# MotorCtrl2.net
KiCad netlist of a schematic drawn in Altium Designer
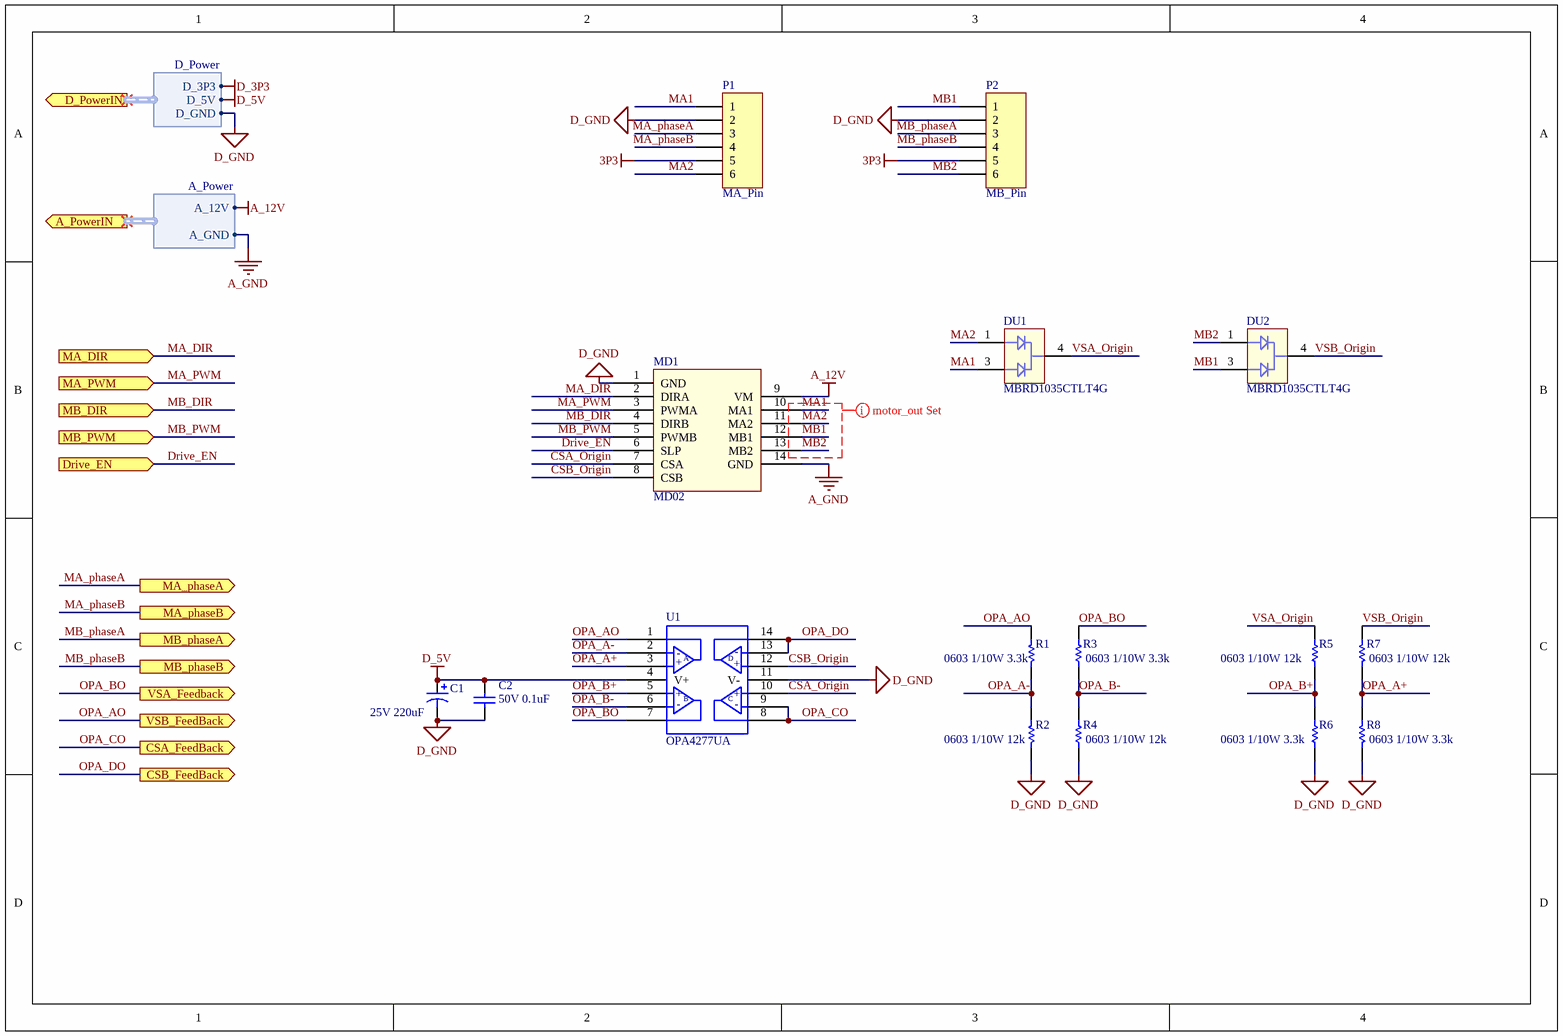
[diagram p0: MotorCtrl2.SchDoc]

(export (version "E")
  (design (tool "Eeschema 10.0.6"))
  (components
    (comp (ref "C1")
      (value "25V 220uF")
      (footprint "OWMR:VZT221M1ETR-0607")
      (fields (field (name "PUBLISHER") "Altium Limited"))
      (libsource (lib "Miscellaneous Devices") (part "Cap Pol1"))
    )
    (comp (ref "C2")
      (value "50V 0.1uF")
      (footprint "OWMR:0603F104M500NT")
      (description "50V 100nF Y5V ±20% 0603 Multilayer Ceramic Capacitors MLCC - SMD/SMT ROHS")
      (fields (field (name "PUBLISHER") "Altium Limited"))
      (libsource (lib "Miscellaneous Devices") (part "Cap Semi"))
    )
    (comp (ref "DU1")
      (value "MBRD1035CTLT4G")
      (footprint "OWMR:MBRD1035CTLT4G")
      (description "35V 470mV@5A 5A TO-252-2(DPAK) Schottky Barrier Diodes (SBD) ROHS")
      (libsource (lib "OWMR") (part "MBRD1035CTLT4G"))
    )
    (comp (ref "DU2")
      (value "MBRD1035CTLT4G")
      (footprint "OWMR:MBRD1035CTLT4G")
      (description "35V 470mV@5A 5A TO-252-2(DPAK) Schottky Barrier Diodes (SBD) ROHS")
      (libsource (lib "OWMR") (part "MBRD1035CTLT4G"))
    )
    (comp (ref "MD1")
      (value "MD02")
      (footprint "OWMR:MOTOR_DRIVER")
      (description "17A 2 Cheel Motor Driver")
      (libsource (lib "OWMR") (part "Motor Driver"))
    )
    (comp (ref "P1")
      (value "MA_Pin")
      (footprint "OWMR:S6B-XH-A")
      (description "S6B-XH-A")
      (fields (field (name "PUBLISHER") "Altium Limited"))
      (libsource (lib "Miscellaneous Connectors") (part "Header 6"))
    )
    (comp (ref "P2")
      (value "MB_Pin")
      (footprint "OWMR:S6B-XH-A")
      (description "S6B-XH-A")
      (fields (field (name "PUBLISHER") "Altium Limited"))
      (libsource (lib "Miscellaneous Connectors") (part "Header 6"))
    )
    (comp (ref "R1")
      (value "0603 1/10W 3.3k")
      (footprint "OWMR:0603WAF3301T5E")
      (fields (field (name "PUBLISHER") "Altium Limited"))
      (libsource (lib "Miscellaneous Devices") (part "Res1"))
    )
    (comp (ref "R2")
      (value "0603 1/10W 12k")
      (footprint "OWMR:PTFR0603B12K0N9")
      (fields (field (name "PUBLISHER") "Altium Limited"))
      (libsource (lib "Miscellaneous Devices") (part "Res1"))
    )
    (comp (ref "R3")
      (value "0603 1/10W 3.3k")
      (footprint "OWMR:0603WAF3301T5E")
      (fields (field (name "PUBLISHER") "Altium Limited"))
      (libsource (lib "Miscellaneous Devices") (part "Res1"))
    )
    (comp (ref "R4")
      (value "0603 1/10W 12k")
      (footprint "OWMR:PTFR0603B12K0N9")
      (fields (field (name "PUBLISHER") "Altium Limited"))
      (libsource (lib "Miscellaneous Devices") (part "Res1"))
    )
    (comp (ref "R5")
      (value "0603 1/10W 12k")
      (footprint "OWMR:PTFR0603B12K0N9")
      (fields (field (name "PUBLISHER") "Altium Limited"))
      (libsource (lib "Miscellaneous Devices") (part "Res1"))
    )
    (comp (ref "R6")
      (value "0603 1/10W 3.3k")
      (footprint "OWMR:0603WAF3301T5E")
      (fields (field (name "PUBLISHER") "Altium Limited"))
      (libsource (lib "Miscellaneous Devices") (part "Res1"))
    )
    (comp (ref "R7")
      (value "0603 1/10W 12k")
      (footprint "OWMR:PTFR0603B12K0N9")
      (fields (field (name "PUBLISHER") "Altium Limited"))
      (libsource (lib "Miscellaneous Devices") (part "Res1"))
    )
    (comp (ref "R8")
      (value "0603 1/10W 3.3k")
      (footprint "OWMR:0603WAF3301T5E")
      (fields (field (name "PUBLISHER") "Altium Limited"))
      (libsource (lib "Miscellaneous Devices") (part "Res1"))
    )
    (comp (ref "U1")
      (value "OPA4277UA")
      (footprint "OWMR:OPA4277UA")
      (description "Small Signal Amplifier")
      (libsource (lib "OWMR") (part "Small Signal Amplifier"))
    )
  )
  (nets
    (net (code "3") (name "/CSA_Origin") (class "Default")
      (node (ref "MD1") (pin "7") (pinfunction "CSA_7") (pintype "passive"))
      (node (ref "U1") (pin "10") (pinfunction "+in_C_10") (pintype "passive"))
    )
    (net (code "4") (name "/CSB_Origin") (class "Default")
      (node (ref "MD1") (pin "8") (pinfunction "CSB_8") (pintype "passive"))
      (node (ref "U1") (pin "12") (pinfunction "+In_D_12") (pintype "passive"))
    )
    (net (code "5") (name "/Drive_EN") (class "Default")
      (node (ref "MD1") (pin "6") (pinfunction "SLP_6") (pintype "passive"))
    )
    (net (code "6") (name "/MA1") (class "Default")
      (node (ref "DU1") (pin "3") (pinfunction "3_3") (pintype "passive"))
      (node (ref "MD1") (pin "10") (pinfunction "MA1_10") (pintype "passive"))
      (node (ref "P1") (pin "1") (pinfunction "1_1") (pintype "passive"))
    )
    (net (code "7") (name "/MA2") (class "Default")
      (node (ref "DU1") (pin "1") (pinfunction "1_1") (pintype "passive"))
      (node (ref "MD1") (pin "11") (pinfunction "MA2_11") (pintype "passive"))
      (node (ref "P1") (pin "6") (pinfunction "6_6") (pintype "passive"))
    )
    (net (code "8") (name "/MA_DIR") (class "Default")
      (node (ref "MD1") (pin "2") (pinfunction "DIRA_2") (pintype "passive"))
    )
    (net (code "9") (name "/MA_PWM") (class "Default")
      (node (ref "MD1") (pin "3") (pinfunction "PWMA_3") (pintype "passive"))
    )
    (net (code "10") (name "/MA_phaseA") (class "Default")
      (node (ref "P1") (pin "3") (pinfunction "3_3") (pintype "passive"))
    )
    (net (code "11") (name "/MA_phaseB") (class "Default")
      (node (ref "P1") (pin "4") (pinfunction "4_4") (pintype "passive"))
    )
    (net (code "12") (name "/MB1") (class "Default")
      (node (ref "DU2") (pin "3") (pinfunction "3_3") (pintype "passive"))
      (node (ref "MD1") (pin "12") (pinfunction "MB1_12") (pintype "passive"))
      (node (ref "P2") (pin "1") (pinfunction "1_1") (pintype "passive"))
    )
    (net (code "13") (name "/MB2") (class "Default")
      (node (ref "DU2") (pin "1") (pinfunction "1_1") (pintype "passive"))
      (node (ref "MD1") (pin "13") (pinfunction "MB2_13") (pintype "passive"))
      (node (ref "P2") (pin "6") (pinfunction "6_6") (pintype "passive"))
    )
    (net (code "14") (name "/MB_DIR") (class "Default")
      (node (ref "MD1") (pin "4") (pinfunction "DIRB_4") (pintype "passive"))
    )
    (net (code "15") (name "/MB_PWM") (class "Default")
      (node (ref "MD1") (pin "5") (pinfunction "PWMB_5") (pintype "passive"))
    )
    (net (code "16") (name "/MB_phaseA") (class "Default")
      (node (ref "P2") (pin "3") (pinfunction "3_3") (pintype "passive"))
    )
    (net (code "17") (name "/MB_phaseB") (class "Default")
      (node (ref "P2") (pin "4") (pinfunction "4_4") (pintype "passive"))
    )
    (net (code "18") (name "/OPA_A+") (class "Default")
      (node (ref "R7") (pin "2") (pinfunction "2_2") (pintype "passive"))
      (node (ref "R8") (pin "1") (pinfunction "1_1") (pintype "passive"))
      (node (ref "U1") (pin "3") (pinfunction "+In_A_3") (pintype "passive"))
    )
    (net (code "19") (name "/OPA_A-") (class "Default")
      (node (ref "R1") (pin "1") (pinfunction "1_1") (pintype "passive"))
      (node (ref "R2") (pin "2") (pinfunction "2_2") (pintype "passive"))
      (node (ref "U1") (pin "2") (pinfunction "-In_A_2") (pintype "passive"))
    )
    (net (code "20") (name "/OPA_AO") (class "Default")
      (node (ref "R1") (pin "2") (pinfunction "2_2") (pintype "passive"))
      (node (ref "U1") (pin "1") (pinfunction "Out_A_1") (pintype "passive"))
    )
    (net (code "21") (name "/OPA_B+") (class "Default")
      (node (ref "R5") (pin "2") (pinfunction "2_2") (pintype "passive"))
      (node (ref "R6") (pin "1") (pinfunction "1_1") (pintype "passive"))
      (node (ref "U1") (pin "5") (pinfunction "+In_B_5") (pintype "passive"))
    )
    (net (code "22") (name "/OPA_B-") (class "Default")
      (node (ref "R3") (pin "1") (pinfunction "1_1") (pintype "passive"))
      (node (ref "R4") (pin "2") (pinfunction "2_2") (pintype "passive"))
      (node (ref "U1") (pin "6") (pinfunction "-In_B_6") (pintype "passive"))
    )
    (net (code "23") (name "/OPA_BO") (class "Default")
      (node (ref "R3") (pin "2") (pinfunction "2_2") (pintype "passive"))
      (node (ref "U1") (pin "7") (pinfunction "Out_B_7") (pintype "passive"))
    )
    (net (code "24") (name "/OPA_CO") (class "Default")
      (node (ref "U1") (pin "8") (pinfunction "Out_C_8") (pintype "passive"))
      (node (ref "U1") (pin "9") (pinfunction "-In_C_9") (pintype "passive"))
    )
    (net (code "25") (name "/OPA_DO") (class "Default")
      (node (ref "U1") (pin "13") (pinfunction "-In_D_13") (pintype "passive"))
      (node (ref "U1") (pin "14") (pinfunction "Out_D_14") (pintype "passive"))
    )
    (net (code "26") (name "/VSA_Origin") (class "Default")
      (node (ref "DU1") (pin "4") (pinfunction "4_4") (pintype "passive"))
      (node (ref "R5") (pin "1") (pinfunction "1_1") (pintype "passive"))
    )
    (net (code "27") (name "/VSB_Origin") (class "Default")
      (node (ref "DU2") (pin "4") (pinfunction "4_4") (pintype "passive"))
      (node (ref "R7") (pin "1") (pinfunction "1_1") (pintype "passive"))
    )
    (net (code "30") (name "3P3") (class "Default")
      (node (ref "P1") (pin "5") (pinfunction "5_5") (pintype "passive"))
      (node (ref "P2") (pin "5") (pinfunction "5_5") (pintype "passive"))
    )
    (net (code "31") (name "A_12V") (class "Default")
      (node (ref "MD1") (pin "9") (pinfunction "VM_9") (pintype "passive"))
    )
    (net (code "32") (name "A_GND") (class "Default")
      (node (ref "MD1") (pin "14") (pinfunction "GND_14") (pintype "passive"))
    )
    (net (code "34") (name "D_5V") (class "Default")
      (node (ref "C1") (pin "1") (pinfunction "1_1") (pintype "passive"))
      (node (ref "C2") (pin "2") (pinfunction "2_2") (pintype "passive"))
      (node (ref "U1") (pin "4") (pinfunction "V+_4") (pintype "passive"))
    )
    (net (code "35") (name "D_GND") (class "Default")
      (node (ref "C1") (pin "2") (pinfunction "2_2") (pintype "passive"))
      (node (ref "C2") (pin "1") (pinfunction "1_1") (pintype "passive"))
      (node (ref "MD1") (pin "1") (pinfunction "GND_1") (pintype "passive"))
      (node (ref "P1") (pin "2") (pinfunction "2_2") (pintype "passive"))
      (node (ref "P2") (pin "2") (pinfunction "2_2") (pintype "passive"))
      (node (ref "R2") (pin "1") (pinfunction "1_1") (pintype "passive"))
      (node (ref "R4") (pin "1") (pinfunction "1_1") (pintype "passive"))
      (node (ref "R6") (pin "2") (pinfunction "2_2") (pintype "passive"))
      (node (ref "R8") (pin "2") (pinfunction "2_2") (pintype "passive"))
      (node (ref "U1") (pin "11") (pinfunction "V-_11") (pintype "passive"))
    )
  )
)
